# FM-Radio-Simple-Receiver-Dip3.net
KiCad netlist of a schematic drawn in EAGLE
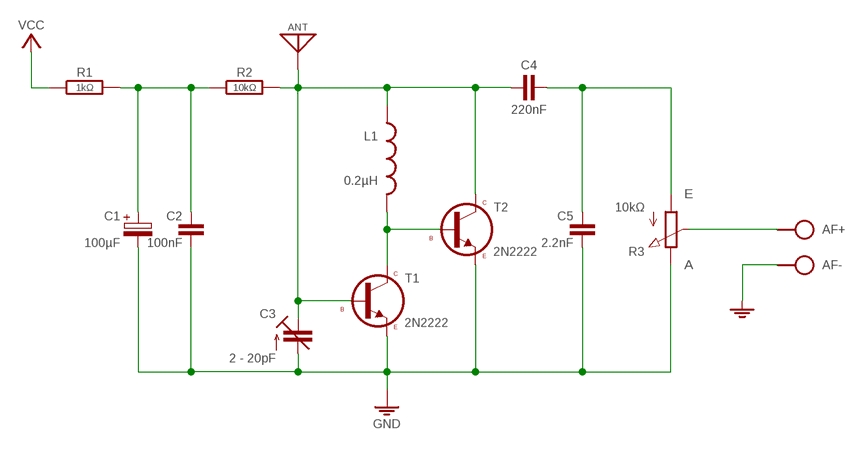
[diagram p0: schematic, sheet 1]

(export (version "E")
  (design (tool "Eeschema 10.0.6"))
  (components
    (comp (ref "AF")
      (value "SPAD+-+-")
      (footprint "eagle-import:SPAD+-")
      (libsource (lib "eagle-import") (part "SPAD+-+-"))
    )
    (comp (ref "ANT")
      (value "ANT")
      (footprint "eagle-import:SPAD")
      (libsource (lib "eagle-import") (part "ANT"))
    )
    (comp (ref "BAT")
      (value "VCC_GNDL")
      (footprint "eagle-import:SPAD-+")
      (libsource (lib "eagle-import") (part "VCC_GNDL"))
    )
    (comp (ref "C1")
      (value "100µF")
      (footprint "eagle-import:E2,5-5_V")
      (libsource (lib "eagle-import") (part "CPOLE2,5-5/V"))
    )
    (comp (ref "C2")
      (value "100nF")
      (footprint "eagle-import:C050-020X036_V")
      (libsource (lib "eagle-import") (part "C050-020X036/V"))
    )
    (comp (ref "C3")
      (value "2 - 20pF")
      (footprint "eagle-import:TRIM-2222-808")
      (libsource (lib "eagle-import") (part "C-TR-PH201272222-808-2PIND"))
    )
    (comp (ref "C4")
      (value "220nF")
      (footprint "eagle-import:C050-020X044")
      (libsource (lib "eagle-import") (part "C-H050-020X044"))
    )
    (comp (ref "C5")
      (value "2.2nF")
      (footprint "eagle-import:C050-020X036_V")
      (libsource (lib "eagle-import") (part "C050-020X036/V"))
    )
    (comp (ref "L1")
      (value "0.2µH")
      (footprint "eagle-import:L-10_10Y")
      (libsource (lib "eagle-import") (part "L10/10Y"))
    )
    (comp (ref "R1")
      (value "1kΩ")
      (footprint "eagle-import:0204_10")
      (libsource (lib "eagle-import") (part "R-H0204/10"))
    )
    (comp (ref "R2")
      (value "10kΩ")
      (footprint "eagle-import:0204_10")
      (libsource (lib "eagle-import") (part "R-H0204/10"))
    )
    (comp (ref "R3")
      (value "10kΩ")
      (footprint "eagle-import:CONN-3P")
      (libsource (lib "eagle-import") (part "POT-3P"))
    )
    (comp (ref "T1")
      (value "2N2222")
      (footprint "eagle-import:TO92")
      (libsource (lib "eagle-import") (part "2N2222"))
    )
    (comp (ref "T2")
      (value "2N2222")
      (footprint "eagle-import:TO92")
      (libsource (lib "eagle-import") (part "2N2222"))
    )
  )
  (nets
    (net (code "1") (name "GND") (class "Default")
      (node (ref "AF") (pin "1") (pinfunction "P$1_1") (pintype "passive"))
      (node (ref "BAT") (pin "1") (pinfunction "GND_1") (pintype "power_in"))
      (node (ref "C1") (pin "-") (pinfunction "-_-") (pintype "passive"))
      (node (ref "C2") (pin "2") (pinfunction "2_2") (pintype "passive"))
      (node (ref "C3") (pin "2") (pinfunction "A_2") (pintype "passive"))
      (node (ref "C5") (pin "2") (pinfunction "2_2") (pintype "passive"))
      (node (ref "R3") (pin "3") (pinfunction "E_3") (pintype "passive"))
      (node (ref "T1") (pin "1") (pinfunction "E_1") (pintype "passive"))
      (node (ref "T2") (pin "1") (pinfunction "E_1") (pintype "passive"))
    )
    (net (code "2") (name "Net-(AFA-P$1)") (class "Default")
      (node (ref "AF") (pin "2") (pinfunction "P$1_2") (pintype "passive"))
      (node (ref "R3") (pin "2") (pinfunction "S_2") (pintype "passive"))
    )
    (net (code "3") (name "Net-(BATA-VCC)") (class "Default")
      (node (ref "BAT") (pin "2") (pinfunction "VCC_2") (pintype "power_in"))
      (node (ref "R1") (pin "1") (pinfunction "1_1") (pintype "passive"))
    )
    (net (code "4") (name "Net-(C1-Pad+)") (class "Default")
      (node (ref "C1") (pin "+") (pinfunction "+_+") (pintype "passive"))
      (node (ref "C2") (pin "1") (pinfunction "1_1") (pintype "passive"))
      (node (ref "R1") (pin "2") (pinfunction "2_2") (pintype "passive"))
      (node (ref "R2") (pin "1") (pinfunction "1_1") (pintype "passive"))
    )
    (net (code "5") (name "Net-(C3-E)") (class "Default")
      (node (ref "ANT") (pin "1") (pinfunction "1_1") (pintype "output"))
      (node (ref "C3") (pin "3") (pinfunction "E_3") (pintype "passive"))
      (node (ref "C4") (pin "1") (pinfunction "1_1") (pintype "passive"))
      (node (ref "L1") (pin "1") (pinfunction "1_1") (pintype "passive"))
      (node (ref "R2") (pin "2") (pinfunction "2_2") (pintype "passive"))
      (node (ref "T1") (pin "2") (pinfunction "B_2") (pintype "passive"))
      (node (ref "T2") (pin "3") (pinfunction "C_3") (pintype "passive"))
    )
    (net (code "6") (name "Net-(R3-A)") (class "Default")
      (node (ref "C4") (pin "2") (pinfunction "2_2") (pintype "passive"))
      (node (ref "C5") (pin "1") (pinfunction "1_1") (pintype "passive"))
      (node (ref "R3") (pin "1") (pinfunction "A_1") (pintype "passive"))
    )
    (net (code "7") (name "Net-(T1-C)") (class "Default")
      (node (ref "L1") (pin "2") (pinfunction "2_2") (pintype "passive"))
      (node (ref "T1") (pin "3") (pinfunction "C_3") (pintype "passive"))
      (node (ref "T2") (pin "2") (pinfunction "B_2") (pintype "passive"))
    )
  )
)
